# QuadCape_SCH.net
KiCad netlist of a schematic drawn in Altium Designer
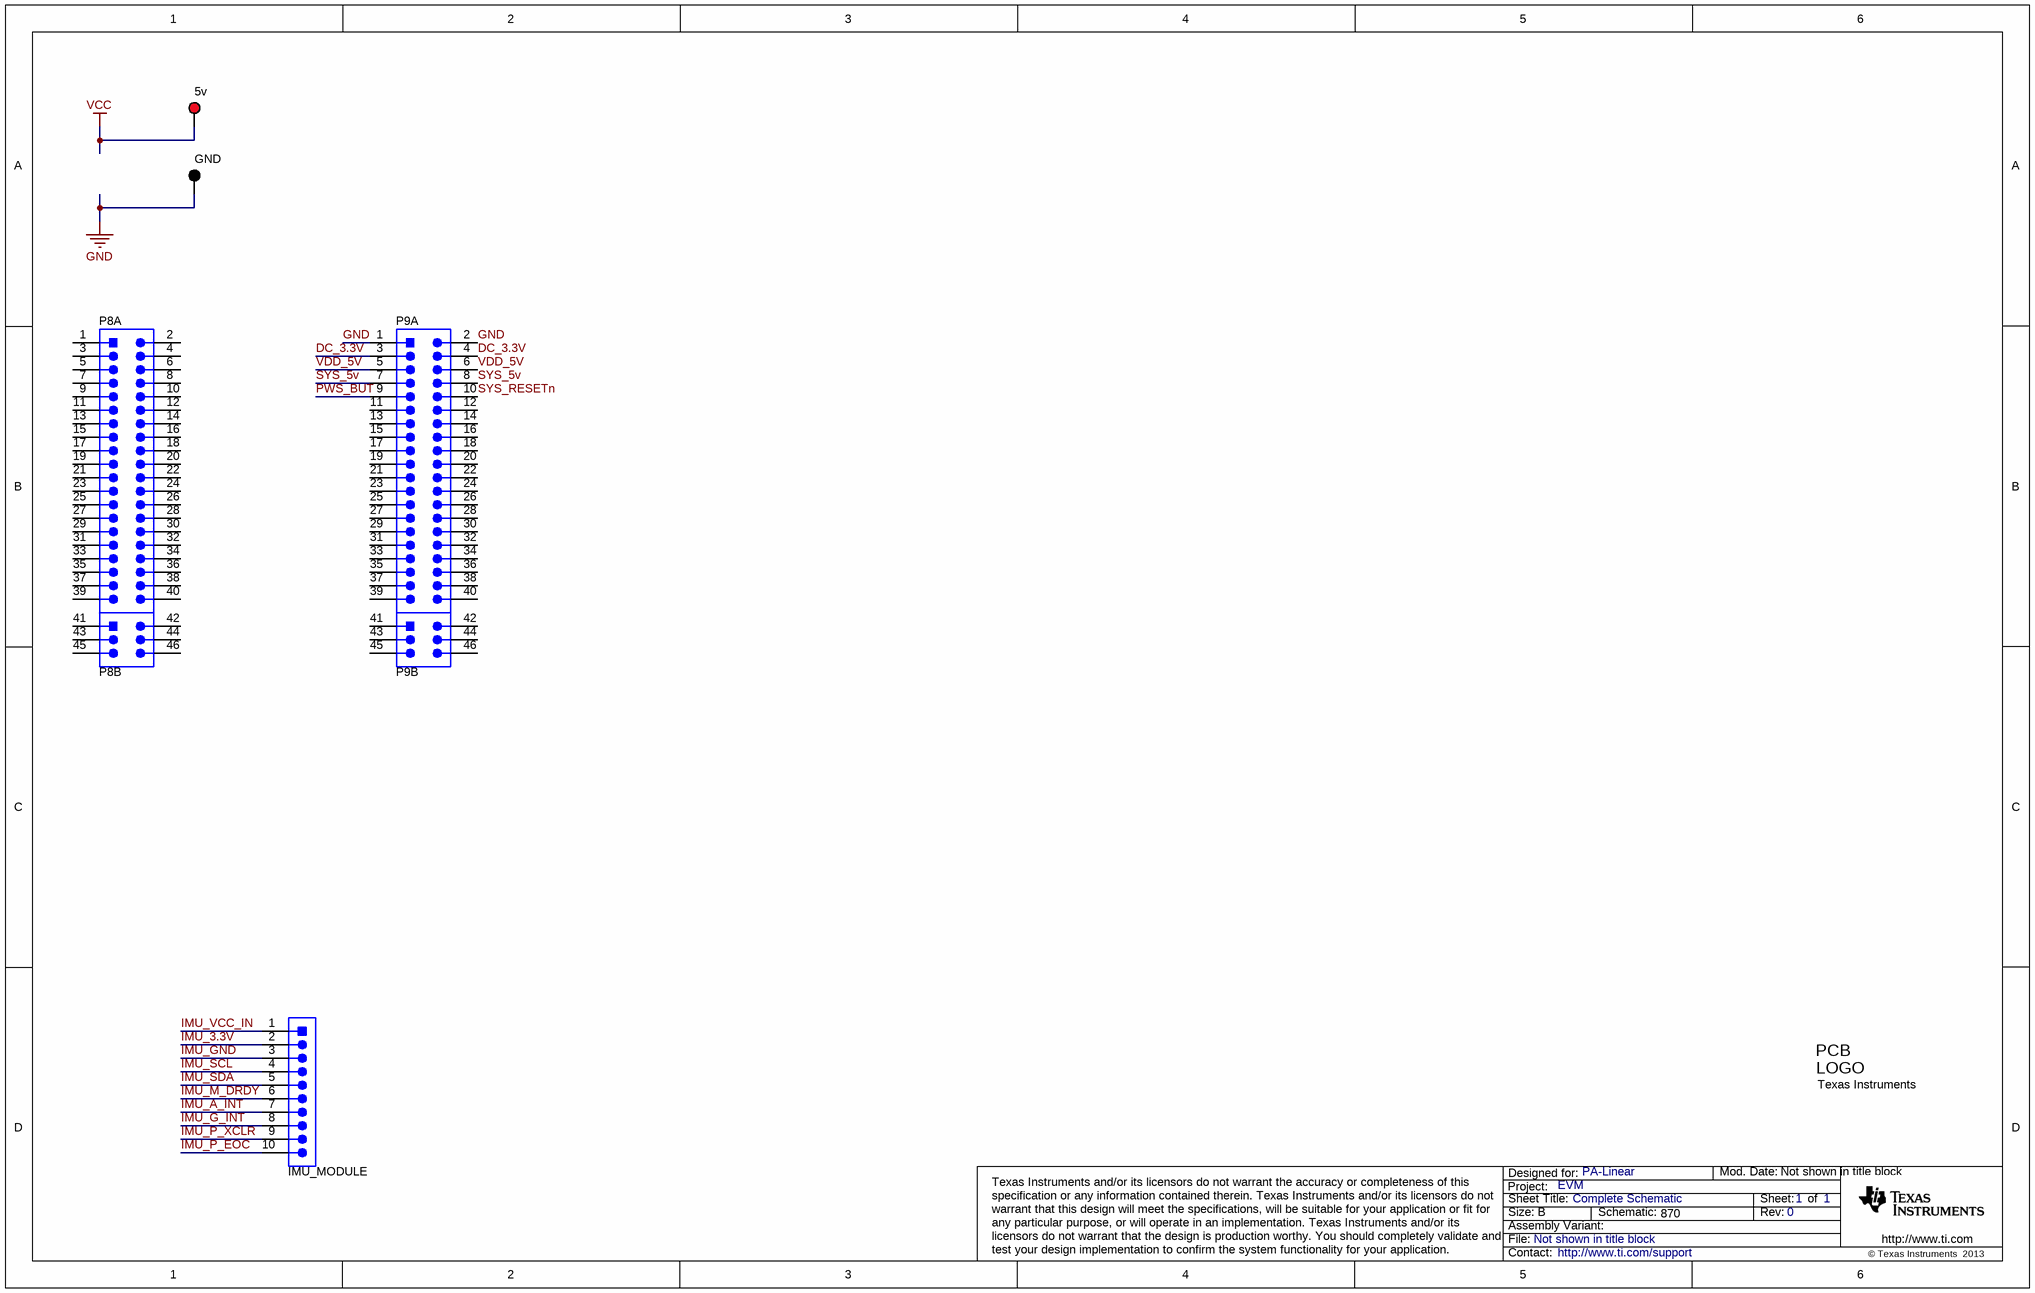
[diagram p0: QuadCape_SCH.SchDoc]

(export (version "E")
  (design (tool "Eeschema 10.0.6"))
  (components
    (comp (ref "5v")
      (value "5005")
      (footprint "Keystone5005")
      (description "Test Point, TH, Compact, Red")
      (fields
        (field (name "MANUFACTURER") "Keystone")
        (field (name "DIGIKEYPARTNUMBER") "5005K-ND")
        (field (name "PUBLISHER") "Texas Instruments")
      )
      (libsource (lib "TemplateSCHLib") (part "5005"))
    )
    (comp (ref "GND")
      (value "5006")
      (footprint "Keystone5006")
      (description "Test Point, TH, Compact, Black")
      (fields
        (field (name "MANUFACTURER") "Keystone")
        (field (name "DIGIKEYPARTNUMBER") "5006K-ND")
        (field (name "PUBLISHER") "Texas Instruments")
      )
      (libsource (lib "TemplateSCHLib") (part "5006"))
    )
    (comp (ref "IMU_MODULE")
      (value "800-10-010-10-001000")
      (footprint "Mill-Max_800-10-010-10-001000")
      (description "Header, 10x1, 100mil, SMT")
      (fields
        (field (name "MANUFACTURER") "Mill-Max")
        (field (name "SYMBOLCREATOR") "a0412235")
        (field (name "PUBLISHER") "Texas Instruments")
      )
      (libsource (lib "Connectors") (part "800-10-010-10-001000"))
    )
    (comp (ref "Logo1")
      (value "Texas Instruments")
      (footprint "TI_Symbol_Overlay_Small")
      (description "Texas Instrument Corporate Signature")
      (fields (field (name "SYMBOLCREATOR") "codlsc") (field (name "PUBLISHER") "Texas Instruments"))
      (libsource (lib "Logos") (part "TI_Logo"))
    )
    (comp (ref "P8A")
      (value "Comment")
      (footprint "TSW-120-07-G-D")
      (description "Header, 100mil, 20x2, Gold, TH")
      (fields
        (field (name "PARTNUMBER") "TSW-120-07-G-D")
        (field (name "MANUFACTURER") "Samtec")
        (field (name "SYMBOLCREATOR") "a0412235")
        (field (name "PUBLISHER") "Texas Instruments")
      )
      (libsource (lib "Connectors") (part "TSW-120-07-G-D"))
    )
    (comp (ref "P8B")
      (value "Comment")
      (footprint "SULLINS_PEC03DAAN")
      (description "Header, 100mil, 3x2, Tin, TH")
      (fields
        (field (name "PARTNUMBER") "PEC03DAAN")
        (field (name "MANUFACTURER") "Sullins Connector Solutions")
        (field (name "SYMBOLCREATOR") "a0412235")
        (field (name "PUBLISHER") "Texas Instruments")
      )
      (libsource (lib "Connectors") (part "PEC03DAAN"))
    )
    (comp (ref "P9A")
      (value "Comment")
      (footprint "TSW-120-07-G-D")
      (description "Header, 100mil, 20x2, Gold, TH")
      (fields
        (field (name "PARTNUMBER") "TSW-120-07-G-D")
        (field (name "MANUFACTURER") "Samtec")
        (field (name "SYMBOLCREATOR") "a0412235")
        (field (name "PUBLISHER") "Texas Instruments")
      )
      (libsource (lib "Connectors") (part "TSW-120-07-G-D"))
    )
    (comp (ref "P9B")
      (value "Comment")
      (footprint "SULLINS_PEC03DAAN")
      (description "Header, 100mil, 3x2, Tin, TH")
      (fields
        (field (name "PARTNUMBER") "PEC03DAAN")
        (field (name "MANUFACTURER") "Sullins Connector Solutions")
        (field (name "SYMBOLCREATOR") "a0412235")
        (field (name "PUBLISHER") "Texas Instruments")
      )
      (libsource (lib "Connectors") (part "PEC03DAAN"))
    )
  )
  (nets
    (net (code "1") (name "/DC_3.3V") (class "Default")
      (node (ref "P9A") (pin "3") (pinfunction "3_3") (pintype "passive"))
      (node (ref "P9A") (pin "4") (pinfunction "4_4") (pintype "passive"))
    )
    (net (code "2") (name "/IMU_3.3V") (class "Default")
      (node (ref "IMU_MODULE") (pin "2") (pinfunction "2_2") (pintype "passive"))
    )
    (net (code "3") (name "/IMU_A_INT") (class "Default")
      (node (ref "IMU_MODULE") (pin "7") (pinfunction "7_7") (pintype "passive"))
    )
    (net (code "4") (name "/IMU_GND") (class "Default")
      (node (ref "IMU_MODULE") (pin "3") (pinfunction "3_3") (pintype "passive"))
    )
    (net (code "5") (name "/IMU_G_INT") (class "Default")
      (node (ref "IMU_MODULE") (pin "8") (pinfunction "8_8") (pintype "passive"))
    )
    (net (code "6") (name "/IMU_M_DRDY") (class "Default")
      (node (ref "IMU_MODULE") (pin "6") (pinfunction "6_6") (pintype "passive"))
    )
    (net (code "7") (name "/IMU_P_EOC") (class "Default")
      (node (ref "IMU_MODULE") (pin "10") (pinfunction "10_10") (pintype "passive"))
    )
    (net (code "8") (name "/IMU_P_XCLR") (class "Default")
      (node (ref "IMU_MODULE") (pin "9") (pinfunction "9_9") (pintype "passive"))
    )
    (net (code "9") (name "/IMU_SCL") (class "Default")
      (node (ref "IMU_MODULE") (pin "4") (pinfunction "4_4") (pintype "passive"))
    )
    (net (code "10") (name "/IMU_SDA") (class "Default")
      (node (ref "IMU_MODULE") (pin "5") (pinfunction "5_5") (pintype "passive"))
    )
    (net (code "11") (name "/IMU_VCC_IN") (class "Default")
      (node (ref "IMU_MODULE") (pin "1") (pinfunction "1_1") (pintype "passive"))
    )
    (net (code "12") (name "/PWS_BUT") (class "Default")
      (node (ref "P9A") (pin "9") (pinfunction "9_9") (pintype "passive"))
    )
    (net (code "13") (name "/SYS_5v") (class "Default")
      (node (ref "P9A") (pin "7") (pinfunction "7_7") (pintype "passive"))
      (node (ref "P9A") (pin "8") (pinfunction "8_8") (pintype "passive"))
    )
    (net (code "14") (name "/SYS_RESETn") (class "Default")
      (node (ref "P9A") (pin "10") (pinfunction "10_10") (pintype "passive"))
    )
    (net (code "15") (name "/VDD_5V") (class "Default")
      (node (ref "P9A") (pin "5") (pinfunction "5_5") (pintype "passive"))
      (node (ref "P9A") (pin "6") (pinfunction "6_6") (pintype "passive"))
    )
    (net (code "16") (name "GND") (class "Default")
      (node (ref "GND") (pin "1") (pintype "passive"))
      (node (ref "P9A") (pin "1") (pinfunction "1_1") (pintype "passive"))
      (node (ref "P9A") (pin "2") (pinfunction "2_2") (pintype "passive"))
    )
    (net (code "17") (name "VCC") (class "Default") (node (ref "5v") (pin "1") (pintype "passive")))
    (net (code "18") (name "unconnected-(P8A-Pad1)") (class "Default")
      (node (ref "P8A") (pin "1") (pinfunction "1_1") (pintype "passive"))
    )
    (net (code "19") (name "unconnected-(P8A-Pad2)") (class "Default")
      (node (ref "P8A") (pin "2") (pinfunction "2_2") (pintype "passive"))
    )
    (net (code "20") (name "unconnected-(P8A-Pad3)") (class "Default")
      (node (ref "P8A") (pin "3") (pinfunction "3_3") (pintype "passive"))
    )
    (net (code "21") (name "unconnected-(P8A-Pad4)") (class "Default")
      (node (ref "P8A") (pin "4") (pinfunction "4_4") (pintype "passive"))
    )
    (net (code "22") (name "unconnected-(P8A-Pad5)") (class "Default")
      (node (ref "P8A") (pin "5") (pinfunction "5_5") (pintype "passive"))
    )
    (net (code "23") (name "unconnected-(P8A-Pad6)") (class "Default")
      (node (ref "P8A") (pin "6") (pinfunction "6_6") (pintype "passive"))
    )
    (net (code "24") (name "unconnected-(P8A-Pad7)") (class "Default")
      (node (ref "P8A") (pin "7") (pinfunction "7_7") (pintype "passive"))
    )
    (net (code "25") (name "unconnected-(P8A-Pad8)") (class "Default")
      (node (ref "P8A") (pin "8") (pinfunction "8_8") (pintype "passive"))
    )
    (net (code "26") (name "unconnected-(P8A-Pad9)") (class "Default")
      (node (ref "P8A") (pin "9") (pinfunction "9_9") (pintype "passive"))
    )
    (net (code "27") (name "unconnected-(P8A-Pad10)") (class "Default")
      (node (ref "P8A") (pin "10") (pinfunction "10_10") (pintype "passive"))
    )
    (net (code "28") (name "unconnected-(P8A-Pad11)") (class "Default")
      (node (ref "P8A") (pin "11") (pinfunction "11_11") (pintype "passive"))
    )
    (net (code "29") (name "unconnected-(P8A-Pad12)") (class "Default")
      (node (ref "P8A") (pin "12") (pinfunction "12_12") (pintype "passive"))
    )
    (net (code "30") (name "unconnected-(P8A-Pad13)") (class "Default")
      (node (ref "P8A") (pin "13") (pinfunction "13_13") (pintype "passive"))
    )
    (net (code "31") (name "unconnected-(P8A-Pad14)") (class "Default")
      (node (ref "P8A") (pin "14") (pinfunction "14_14") (pintype "passive"))
    )
    (net (code "32") (name "unconnected-(P8A-Pad15)") (class "Default")
      (node (ref "P8A") (pin "15") (pinfunction "15_15") (pintype "passive"))
    )
    (net (code "33") (name "unconnected-(P8A-Pad16)") (class "Default")
      (node (ref "P8A") (pin "16") (pinfunction "16_16") (pintype "passive"))
    )
    (net (code "34") (name "unconnected-(P8A-Pad17)") (class "Default")
      (node (ref "P8A") (pin "17") (pinfunction "17_17") (pintype "passive"))
    )
    (net (code "35") (name "unconnected-(P8A-Pad18)") (class "Default")
      (node (ref "P8A") (pin "18") (pinfunction "18_18") (pintype "passive"))
    )
    (net (code "36") (name "unconnected-(P8A-Pad19)") (class "Default")
      (node (ref "P8A") (pin "19") (pinfunction "19_19") (pintype "passive"))
    )
    (net (code "37") (name "unconnected-(P8A-Pad20)") (class "Default")
      (node (ref "P8A") (pin "20") (pinfunction "20_20") (pintype "passive"))
    )
    (net (code "38") (name "unconnected-(P8A-Pad21)") (class "Default")
      (node (ref "P8A") (pin "21") (pinfunction "21_21") (pintype "passive"))
    )
    (net (code "39") (name "unconnected-(P8A-Pad22)") (class "Default")
      (node (ref "P8A") (pin "22") (pinfunction "22_22") (pintype "passive"))
    )
    (net (code "40") (name "unconnected-(P8A-Pad23)") (class "Default")
      (node (ref "P8A") (pin "23") (pinfunction "23_23") (pintype "passive"))
    )
    (net (code "41") (name "unconnected-(P8A-Pad24)") (class "Default")
      (node (ref "P8A") (pin "24") (pinfunction "24_24") (pintype "passive"))
    )
    (net (code "42") (name "unconnected-(P8A-Pad25)") (class "Default")
      (node (ref "P8A") (pin "25") (pinfunction "25_25") (pintype "passive"))
    )
    (net (code "43") (name "unconnected-(P8A-Pad26)") (class "Default")
      (node (ref "P8A") (pin "26") (pinfunction "26_26") (pintype "passive"))
    )
    (net (code "44") (name "unconnected-(P8A-Pad27)") (class "Default")
      (node (ref "P8A") (pin "27") (pinfunction "27_27") (pintype "passive"))
    )
    (net (code "45") (name "unconnected-(P8A-Pad28)") (class "Default")
      (node (ref "P8A") (pin "28") (pinfunction "28_28") (pintype "passive"))
    )
    (net (code "46") (name "unconnected-(P8A-Pad29)") (class "Default")
      (node (ref "P8A") (pin "29") (pinfunction "29_29") (pintype "passive"))
    )
    (net (code "47") (name "unconnected-(P8A-Pad30)") (class "Default")
      (node (ref "P8A") (pin "30") (pinfunction "30_30") (pintype "passive"))
    )
    (net (code "48") (name "unconnected-(P8A-Pad31)") (class "Default")
      (node (ref "P8A") (pin "31") (pinfunction "31_31") (pintype "passive"))
    )
    (net (code "49") (name "unconnected-(P8A-Pad32)") (class "Default")
      (node (ref "P8A") (pin "32") (pinfunction "32_32") (pintype "passive"))
    )
    (net (code "50") (name "unconnected-(P8A-Pad33)") (class "Default")
      (node (ref "P8A") (pin "33") (pinfunction "33_33") (pintype "passive"))
    )
    (net (code "51") (name "unconnected-(P8A-Pad34)") (class "Default")
      (node (ref "P8A") (pin "34") (pinfunction "34_34") (pintype "passive"))
    )
    (net (code "52") (name "unconnected-(P8A-Pad35)") (class "Default")
      (node (ref "P8A") (pin "35") (pinfunction "35_35") (pintype "passive"))
    )
    (net (code "53") (name "unconnected-(P8A-Pad36)") (class "Default")
      (node (ref "P8A") (pin "36") (pinfunction "36_36") (pintype "passive"))
    )
    (net (code "54") (name "unconnected-(P8A-Pad37)") (class "Default")
      (node (ref "P8A") (pin "37") (pinfunction "37_37") (pintype "passive"))
    )
    (net (code "55") (name "unconnected-(P8A-Pad38)") (class "Default")
      (node (ref "P8A") (pin "38") (pinfunction "38_38") (pintype "passive"))
    )
    (net (code "56") (name "unconnected-(P8A-Pad39)") (class "Default")
      (node (ref "P8A") (pin "39") (pinfunction "39_39") (pintype "passive"))
    )
    (net (code "57") (name "unconnected-(P8A-Pad40)") (class "Default")
      (node (ref "P8A") (pin "40") (pinfunction "40_40") (pintype "passive"))
    )
    (net (code "58") (name "unconnected-(P8B-Pad41)") (class "Default")
      (node (ref "P8B") (pin "41") (pinfunction "41_41") (pintype "passive"))
    )
    (net (code "59") (name "unconnected-(P8B-Pad42)") (class "Default")
      (node (ref "P8B") (pin "42") (pinfunction "42_42") (pintype "passive"))
    )
    (net (code "60") (name "unconnected-(P8B-Pad43)") (class "Default")
      (node (ref "P8B") (pin "43") (pinfunction "43_43") (pintype "passive"))
    )
    (net (code "61") (name "unconnected-(P8B-Pad44)") (class "Default")
      (node (ref "P8B") (pin "44") (pinfunction "44_44") (pintype "passive"))
    )
    (net (code "62") (name "unconnected-(P8B-Pad45)") (class "Default")
      (node (ref "P8B") (pin "45") (pinfunction "45_45") (pintype "passive"))
    )
    (net (code "63") (name "unconnected-(P8B-Pad46)") (class "Default")
      (node (ref "P8B") (pin "46") (pinfunction "46_46") (pintype "passive"))
    )
    (net (code "64") (name "unconnected-(P9A-Pad11)") (class "Default")
      (node (ref "P9A") (pin "11") (pinfunction "11_11") (pintype "passive"))
    )
    (net (code "65") (name "unconnected-(P9A-Pad12)") (class "Default")
      (node (ref "P9A") (pin "12") (pinfunction "12_12") (pintype "passive"))
    )
    (net (code "66") (name "unconnected-(P9A-Pad13)") (class "Default")
      (node (ref "P9A") (pin "13") (pinfunction "13_13") (pintype "passive"))
    )
    (net (code "67") (name "unconnected-(P9A-Pad14)") (class "Default")
      (node (ref "P9A") (pin "14") (pinfunction "14_14") (pintype "passive"))
    )
    (net (code "68") (name "unconnected-(P9A-Pad15)") (class "Default")
      (node (ref "P9A") (pin "15") (pinfunction "15_15") (pintype "passive"))
    )
    (net (code "69") (name "unconnected-(P9A-Pad16)") (class "Default")
      (node (ref "P9A") (pin "16") (pinfunction "16_16") (pintype "passive"))
    )
    (net (code "70") (name "unconnected-(P9A-Pad17)") (class "Default")
      (node (ref "P9A") (pin "17") (pinfunction "17_17") (pintype "passive"))
    )
    (net (code "71") (name "unconnected-(P9A-Pad18)") (class "Default")
      (node (ref "P9A") (pin "18") (pinfunction "18_18") (pintype "passive"))
    )
    (net (code "72") (name "unconnected-(P9A-Pad19)") (class "Default")
      (node (ref "P9A") (pin "19") (pinfunction "19_19") (pintype "passive"))
    )
    (net (code "73") (name "unconnected-(P9A-Pad20)") (class "Default")
      (node (ref "P9A") (pin "20") (pinfunction "20_20") (pintype "passive"))
    )
    (net (code "74") (name "unconnected-(P9A-Pad21)") (class "Default")
      (node (ref "P9A") (pin "21") (pinfunction "21_21") (pintype "passive"))
    )
    (net (code "75") (name "unconnected-(P9A-Pad22)") (class "Default")
      (node (ref "P9A") (pin "22") (pinfunction "22_22") (pintype "passive"))
    )
    (net (code "76") (name "unconnected-(P9A-Pad23)") (class "Default")
      (node (ref "P9A") (pin "23") (pinfunction "23_23") (pintype "passive"))
    )
    (net (code "77") (name "unconnected-(P9A-Pad24)") (class "Default")
      (node (ref "P9A") (pin "24") (pinfunction "24_24") (pintype "passive"))
    )
    (net (code "78") (name "unconnected-(P9A-Pad25)") (class "Default")
      (node (ref "P9A") (pin "25") (pinfunction "25_25") (pintype "passive"))
    )
    (net (code "79") (name "unconnected-(P9A-Pad26)") (class "Default")
      (node (ref "P9A") (pin "26") (pinfunction "26_26") (pintype "passive"))
    )
    (net (code "80") (name "unconnected-(P9A-Pad27)") (class "Default")
      (node (ref "P9A") (pin "27") (pinfunction "27_27") (pintype "passive"))
    )
    (net (code "81") (name "unconnected-(P9A-Pad28)") (class "Default")
      (node (ref "P9A") (pin "28") (pinfunction "28_28") (pintype "passive"))
    )
    (net (code "82") (name "unconnected-(P9A-Pad29)") (class "Default")
      (node (ref "P9A") (pin "29") (pinfunction "29_29") (pintype "passive"))
    )
    (net (code "83") (name "unconnected-(P9A-Pad30)") (class "Default")
      (node (ref "P9A") (pin "30") (pinfunction "30_30") (pintype "passive"))
    )
    (net (code "84") (name "unconnected-(P9A-Pad31)") (class "Default")
      (node (ref "P9A") (pin "31") (pinfunction "31_31") (pintype "passive"))
    )
    (net (code "85") (name "unconnected-(P9A-Pad32)") (class "Default")
      (node (ref "P9A") (pin "32") (pinfunction "32_32") (pintype "passive"))
    )
    (net (code "86") (name "unconnected-(P9A-Pad33)") (class "Default")
      (node (ref "P9A") (pin "33") (pinfunction "33_33") (pintype "passive"))
    )
    (net (code "87") (name "unconnected-(P9A-Pad34)") (class "Default")
      (node (ref "P9A") (pin "34") (pinfunction "34_34") (pintype "passive"))
    )
    (net (code "88") (name "unconnected-(P9A-Pad35)") (class "Default")
      (node (ref "P9A") (pin "35") (pinfunction "35_35") (pintype "passive"))
    )
    (net (code "89") (name "unconnected-(P9A-Pad36)") (class "Default")
      (node (ref "P9A") (pin "36") (pinfunction "36_36") (pintype "passive"))
    )
    (net (code "90") (name "unconnected-(P9A-Pad37)") (class "Default")
      (node (ref "P9A") (pin "37") (pinfunction "37_37") (pintype "passive"))
    )
    (net (code "91") (name "unconnected-(P9A-Pad38)") (class "Default")
      (node (ref "P9A") (pin "38") (pinfunction "38_38") (pintype "passive"))
    )
    (net (code "92") (name "unconnected-(P9A-Pad39)") (class "Default")
      (node (ref "P9A") (pin "39") (pinfunction "39_39") (pintype "passive"))
    )
    (net (code "93") (name "unconnected-(P9A-Pad40)") (class "Default")
      (node (ref "P9A") (pin "40") (pinfunction "40_40") (pintype "passive"))
    )
    (net (code "94") (name "unconnected-(P9B-Pad41)") (class "Default")
      (node (ref "P9B") (pin "41") (pinfunction "41_41") (pintype "passive"))
    )
    (net (code "95") (name "unconnected-(P9B-Pad42)") (class "Default")
      (node (ref "P9B") (pin "42") (pinfunction "42_42") (pintype "passive"))
    )
    (net (code "96") (name "unconnected-(P9B-Pad43)") (class "Default")
      (node (ref "P9B") (pin "43") (pinfunction "43_43") (pintype "passive"))
    )
    (net (code "97") (name "unconnected-(P9B-Pad44)") (class "Default")
      (node (ref "P9B") (pin "44") (pinfunction "44_44") (pintype "passive"))
    )
    (net (code "98") (name "unconnected-(P9B-Pad45)") (class "Default")
      (node (ref "P9B") (pin "45") (pinfunction "45_45") (pintype "passive"))
    )
    (net (code "99") (name "unconnected-(P9B-Pad46)") (class "Default")
      (node (ref "P9B") (pin "46") (pinfunction "46_46") (pintype "passive"))
    )
  )
)
